# MOSFET_BANK.net
KiCad netlist of a schematic drawn in Altium Designer
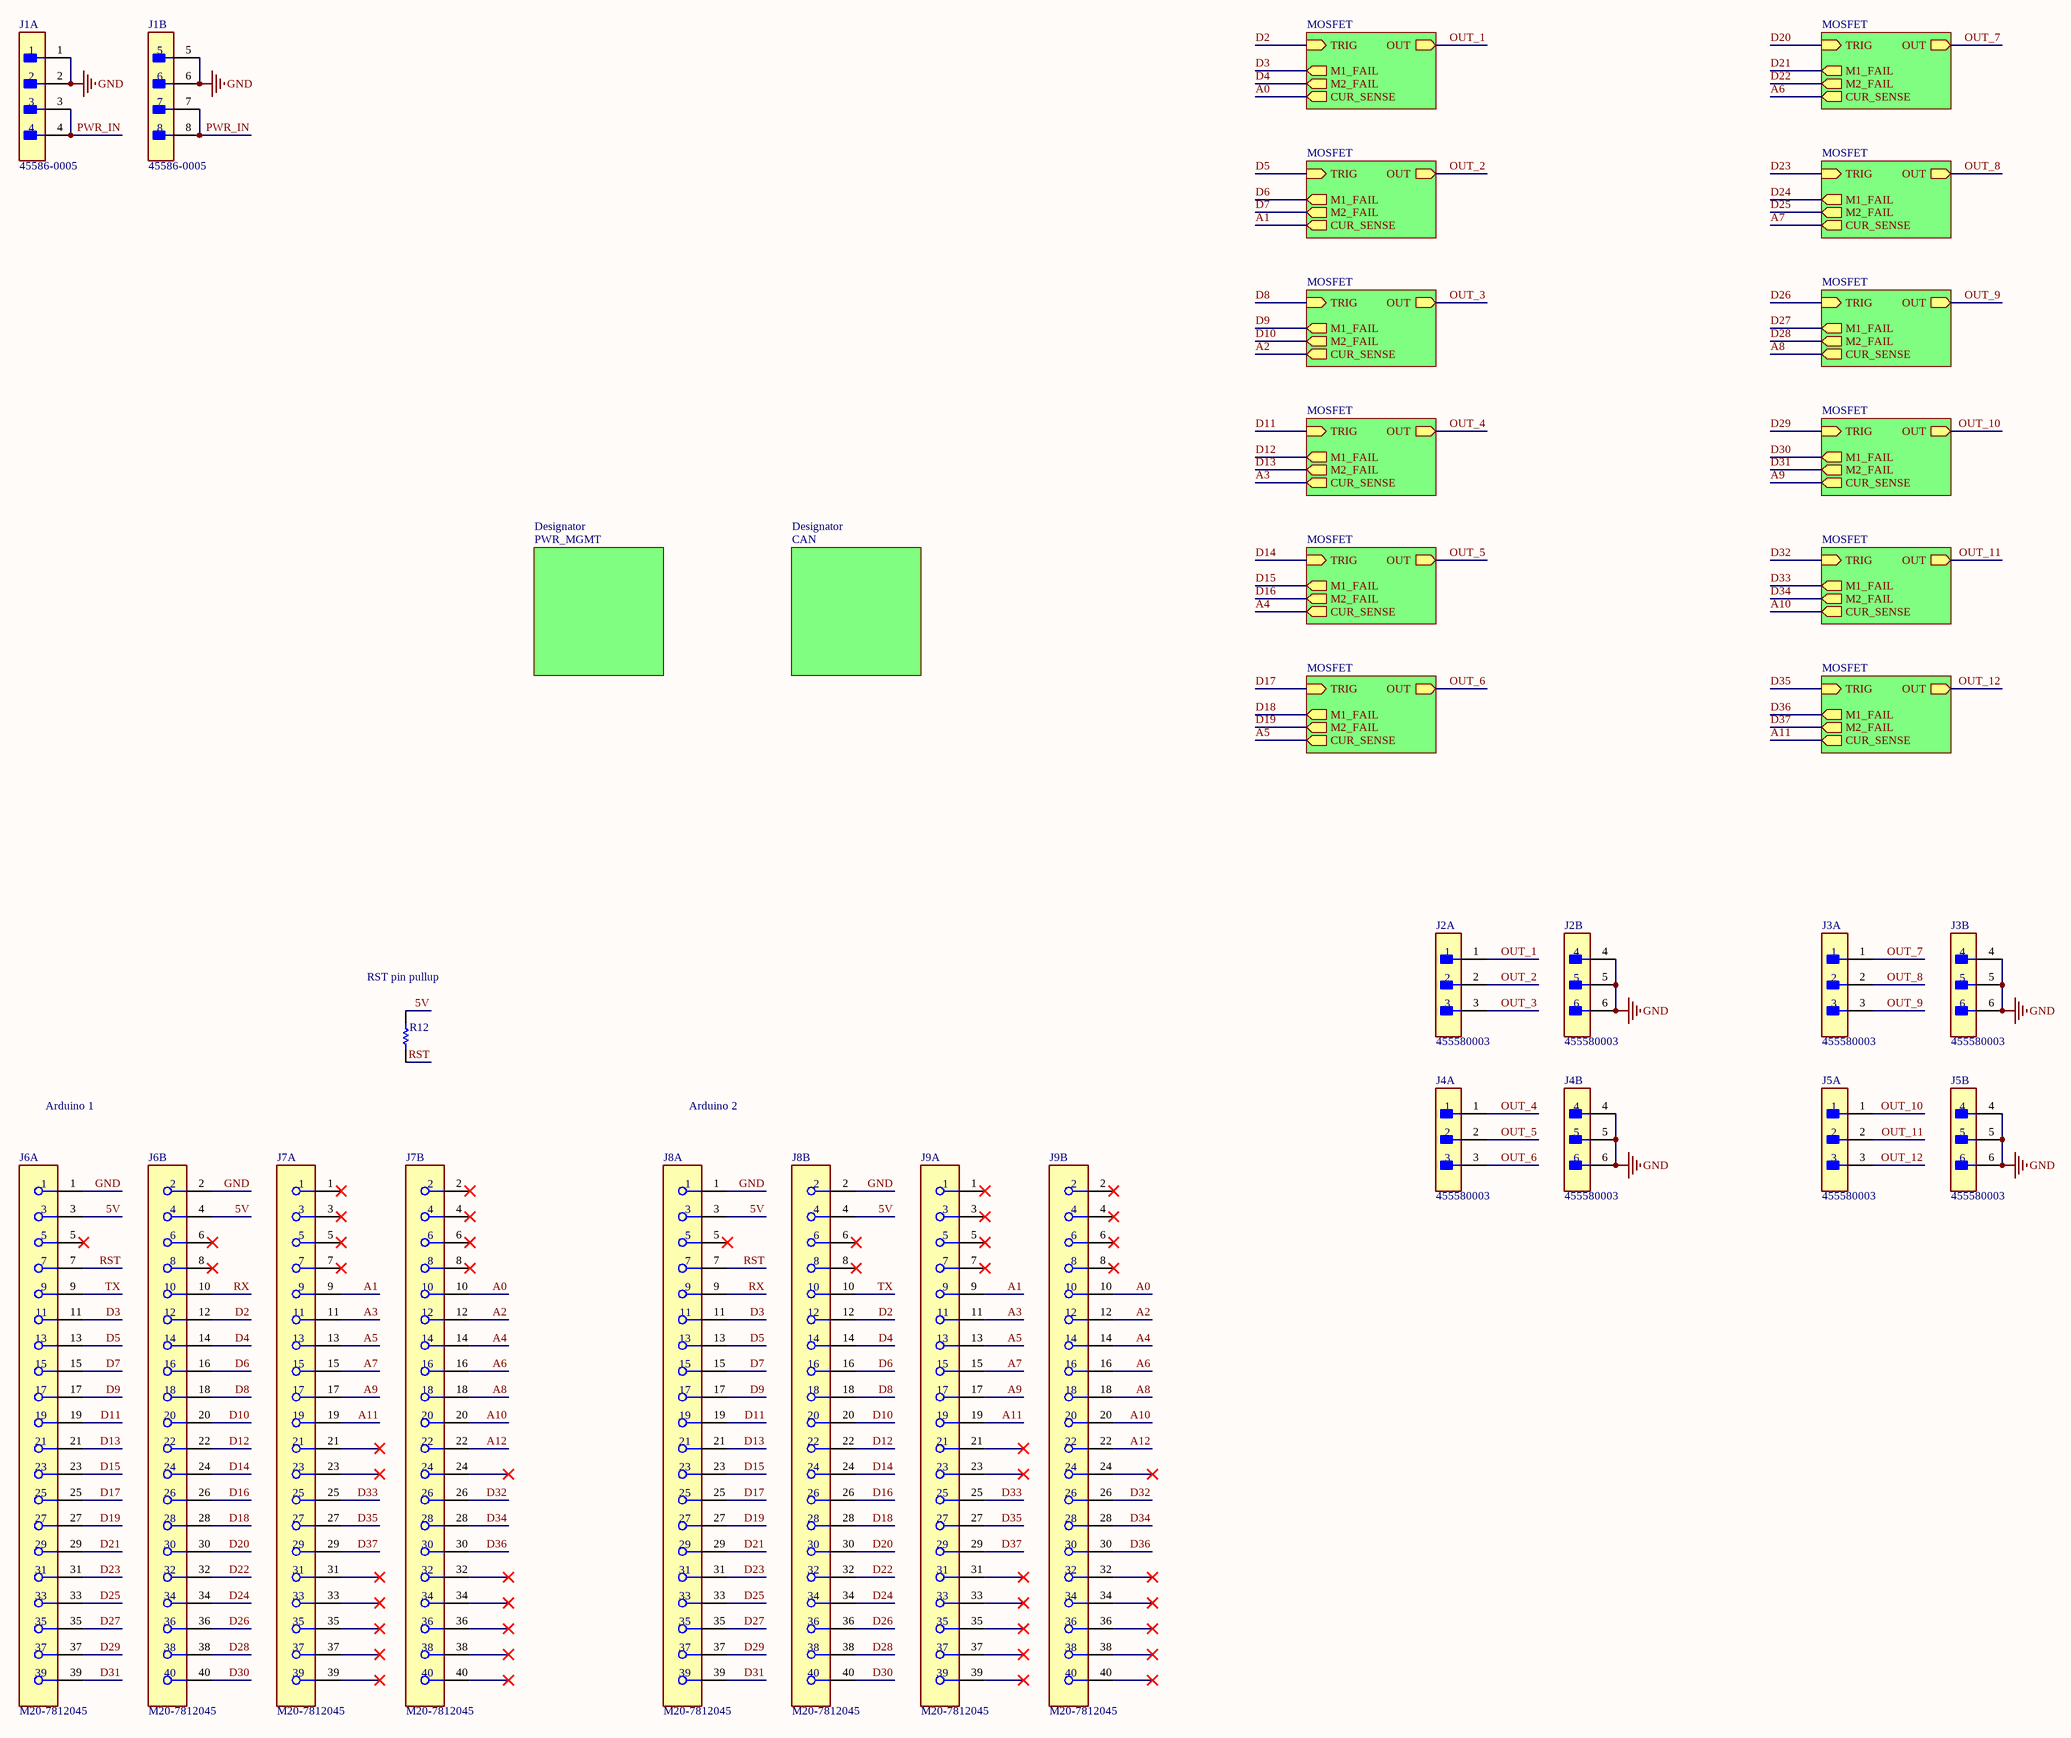
[diagram p0: MOSFET_BANK.SchDoc]

(export (version "E")
  (design (tool "Eeschema 10.0.6"))
  (components
    (comp (ref "J1")
      (value "45586-0005")
      (footprint "FP-45586-0005-MFG")
      (description "CONN HEADER R/A 8POS 4.2MM")
      (libsource (lib "Altium Content Vault") (part "85438c39ca9ef07d43bb2e97c52bc44"))
    )
    (comp (ref "J2")
      (value "455580003")
      (footprint "FP-455580003-MFG")
      (description "CONN HEADER R/A 6POS 4.2MM")
      (fields
        (field (name "OCTOPART") "https://octopart.com/45558-0003-molex-7672845")
        (field (name "MANUFACTURER") "Molex")
      )
      (libsource (lib "Altium Content Vault") (part "bb9cbdb24149a20ba329b4e86909569"))
    )
    (comp (ref "J3")
      (value "455580003")
      (footprint "FP-455580003-MFG")
      (description "CONN HEADER R/A 6POS 4.2MM")
      (fields
        (field (name "OCTOPART") "https://octopart.com/45558-0003-molex-7672845")
        (field (name "MANUFACTURER") "Molex")
      )
      (libsource (lib "Altium Content Vault") (part "bb9cbdb24149a20ba329b4e86909569"))
    )
    (comp (ref "J4")
      (value "455580003")
      (footprint "FP-455580003-MFG")
      (description "CONN HEADER R/A 6POS 4.2MM")
      (fields
        (field (name "OCTOPART") "https://octopart.com/45558-0003-molex-7672845")
        (field (name "MANUFACTURER") "Molex")
      )
      (libsource (lib "Altium Content Vault") (part "bb9cbdb24149a20ba329b4e86909569"))
    )
    (comp (ref "J5")
      (value "455580003")
      (footprint "FP-455580003-MFG")
      (description "CONN HEADER R/A 6POS 4.2MM")
      (fields
        (field (name "OCTOPART") "https://octopart.com/45558-0003-molex-7672845")
        (field (name "MANUFACTURER") "Molex")
      )
      (libsource (lib "Altium Content Vault") (part "bb9cbdb24149a20ba329b4e86909569"))
    )
    (comp (ref "J6")
      (value "M20-7812045")
      (footprint "FP-M20-7812045-MFG")
      (description "CONN RCPT 40POS 0.1 GOLD SMD")
      (libsource (lib "Altium Content Vault") (part "7acf1c4a8db21028d11741a46a6ec78"))
    )
    (comp (ref "J7")
      (value "M20-7812045")
      (footprint "FP-M20-7812045-MFG")
      (description "CONN RCPT 40POS 0.1 GOLD SMD")
      (libsource (lib "Altium Content Vault") (part "7acf1c4a8db21028d11741a46a6ec78"))
    )
    (comp (ref "J8")
      (value "M20-7812045")
      (footprint "FP-M20-7812045-MFG")
      (description "CONN RCPT 40POS 0.1 GOLD SMD")
      (libsource (lib "Altium Content Vault") (part "7acf1c4a8db21028d11741a46a6ec78"))
    )
    (comp (ref "J9")
      (value "M20-7812045")
      (footprint "FP-M20-7812045-MFG")
      (description "CONN RCPT 40POS 0.1 GOLD SMD")
      (libsource (lib "Altium Content Vault") (part "7acf1c4a8db21028d11741a46a6ec78"))
    )
    (comp (ref "R12")
      (value "ERJ3EKF1002V")
      (footprint "RESC1609X55X30LL15T15")
      (description "Chip Resistor, 10 KOhm, +/- 1%, 0.1 W, -55 to 155 degC, 0603 (1608 Metric), RoHS, Tape and Reel")
      (fields (field (name "TOLERANCE") "1%") (field (name "MANUFACTURER") "Panasonic"))
      (libsource (lib "Altium Content Vault") (part "RES-2"))
    )
  )
  (nets
    (net (code "1") (name "/5V") (class "Default")
      (node (ref "J6") (pin "3") (pinfunction "3_3") (pintype "passive"))
      (node (ref "J6") (pin "4") (pinfunction "4_4") (pintype "passive"))
      (node (ref "J8") (pin "3") (pinfunction "3_3") (pintype "passive"))
      (node (ref "J8") (pin "4") (pinfunction "4_4") (pintype "passive"))
      (node (ref "R12") (pin "2") (pinfunction "2_2") (pintype "passive"))
    )
    (net (code "2") (name "/A0") (class "Default")
      (node (ref "J7") (pin "10") (pinfunction "10_10") (pintype "passive"))
      (node (ref "J9") (pin "10") (pinfunction "10_10") (pintype "passive"))
    )
    (net (code "3") (name "/A1") (class "Default")
      (node (ref "J7") (pin "9") (pinfunction "9_9") (pintype "passive"))
      (node (ref "J9") (pin "9") (pinfunction "9_9") (pintype "passive"))
    )
    (net (code "4") (name "/A2") (class "Default")
      (node (ref "J7") (pin "12") (pinfunction "12_12") (pintype "passive"))
      (node (ref "J9") (pin "12") (pinfunction "12_12") (pintype "passive"))
    )
    (net (code "5") (name "/A3") (class "Default")
      (node (ref "J7") (pin "11") (pinfunction "11_11") (pintype "passive"))
      (node (ref "J9") (pin "11") (pinfunction "11_11") (pintype "passive"))
    )
    (net (code "6") (name "/A4") (class "Default")
      (node (ref "J7") (pin "14") (pinfunction "14_14") (pintype "passive"))
      (node (ref "J9") (pin "14") (pinfunction "14_14") (pintype "passive"))
    )
    (net (code "7") (name "/A5") (class "Default")
      (node (ref "J7") (pin "13") (pinfunction "13_13") (pintype "passive"))
      (node (ref "J9") (pin "13") (pinfunction "13_13") (pintype "passive"))
    )
    (net (code "8") (name "/A6") (class "Default")
      (node (ref "J7") (pin "16") (pinfunction "16_16") (pintype "passive"))
      (node (ref "J9") (pin "16") (pinfunction "16_16") (pintype "passive"))
    )
    (net (code "9") (name "/A7") (class "Default")
      (node (ref "J7") (pin "15") (pinfunction "15_15") (pintype "passive"))
      (node (ref "J9") (pin "15") (pinfunction "15_15") (pintype "passive"))
    )
    (net (code "10") (name "/A8") (class "Default")
      (node (ref "J7") (pin "18") (pinfunction "18_18") (pintype "passive"))
      (node (ref "J9") (pin "18") (pinfunction "18_18") (pintype "passive"))
    )
    (net (code "11") (name "/A9") (class "Default")
      (node (ref "J7") (pin "17") (pinfunction "17_17") (pintype "passive"))
      (node (ref "J9") (pin "17") (pinfunction "17_17") (pintype "passive"))
    )
    (net (code "12") (name "/A10") (class "Default")
      (node (ref "J7") (pin "20") (pinfunction "20_20") (pintype "passive"))
      (node (ref "J9") (pin "20") (pinfunction "20_20") (pintype "passive"))
    )
    (net (code "13") (name "/A11") (class "Default")
      (node (ref "J7") (pin "19") (pinfunction "19_19") (pintype "passive"))
      (node (ref "J9") (pin "19") (pinfunction "19_19") (pintype "passive"))
    )
    (net (code "14") (name "/A12") (class "Default")
      (node (ref "J7") (pin "22") (pinfunction "22_22") (pintype "passive"))
      (node (ref "J9") (pin "22") (pinfunction "22_22") (pintype "passive"))
    )
    (net (code "15") (name "/D2") (class "Default")
      (node (ref "J6") (pin "12") (pinfunction "12_12") (pintype "passive"))
      (node (ref "J8") (pin "12") (pinfunction "12_12") (pintype "passive"))
    )
    (net (code "16") (name "/D3") (class "Default")
      (node (ref "J6") (pin "11") (pinfunction "11_11") (pintype "passive"))
      (node (ref "J8") (pin "11") (pinfunction "11_11") (pintype "passive"))
    )
    (net (code "17") (name "/D4") (class "Default")
      (node (ref "J6") (pin "14") (pinfunction "14_14") (pintype "passive"))
      (node (ref "J8") (pin "14") (pinfunction "14_14") (pintype "passive"))
    )
    (net (code "18") (name "/D5") (class "Default")
      (node (ref "J6") (pin "13") (pinfunction "13_13") (pintype "passive"))
      (node (ref "J8") (pin "13") (pinfunction "13_13") (pintype "passive"))
    )
    (net (code "19") (name "/D6") (class "Default")
      (node (ref "J6") (pin "16") (pinfunction "16_16") (pintype "passive"))
      (node (ref "J8") (pin "16") (pinfunction "16_16") (pintype "passive"))
    )
    (net (code "20") (name "/D7") (class "Default")
      (node (ref "J6") (pin "15") (pinfunction "15_15") (pintype "passive"))
      (node (ref "J8") (pin "15") (pinfunction "15_15") (pintype "passive"))
    )
    (net (code "21") (name "/D8") (class "Default")
      (node (ref "J6") (pin "18") (pinfunction "18_18") (pintype "passive"))
      (node (ref "J8") (pin "18") (pinfunction "18_18") (pintype "passive"))
    )
    (net (code "22") (name "/D9") (class "Default")
      (node (ref "J6") (pin "17") (pinfunction "17_17") (pintype "passive"))
      (node (ref "J8") (pin "17") (pinfunction "17_17") (pintype "passive"))
    )
    (net (code "23") (name "/D10") (class "Default")
      (node (ref "J6") (pin "20") (pinfunction "20_20") (pintype "passive"))
      (node (ref "J8") (pin "20") (pinfunction "20_20") (pintype "passive"))
    )
    (net (code "24") (name "/D11") (class "Default")
      (node (ref "J6") (pin "19") (pinfunction "19_19") (pintype "passive"))
      (node (ref "J8") (pin "19") (pinfunction "19_19") (pintype "passive"))
    )
    (net (code "25") (name "/D12") (class "Default")
      (node (ref "J6") (pin "22") (pinfunction "22_22") (pintype "passive"))
      (node (ref "J8") (pin "22") (pinfunction "22_22") (pintype "passive"))
    )
    (net (code "26") (name "/D13") (class "Default")
      (node (ref "J6") (pin "21") (pinfunction "21_21") (pintype "passive"))
      (node (ref "J8") (pin "21") (pinfunction "21_21") (pintype "passive"))
    )
    (net (code "27") (name "/D14") (class "Default")
      (node (ref "J6") (pin "24") (pinfunction "24_24") (pintype "passive"))
      (node (ref "J8") (pin "24") (pinfunction "24_24") (pintype "passive"))
    )
    (net (code "28") (name "/D15") (class "Default")
      (node (ref "J6") (pin "23") (pinfunction "23_23") (pintype "passive"))
      (node (ref "J8") (pin "23") (pinfunction "23_23") (pintype "passive"))
    )
    (net (code "29") (name "/D16") (class "Default")
      (node (ref "J6") (pin "26") (pinfunction "26_26") (pintype "passive"))
      (node (ref "J8") (pin "26") (pinfunction "26_26") (pintype "passive"))
    )
    (net (code "30") (name "/D17") (class "Default")
      (node (ref "J6") (pin "25") (pinfunction "25_25") (pintype "passive"))
      (node (ref "J8") (pin "25") (pinfunction "25_25") (pintype "passive"))
    )
    (net (code "31") (name "/D18") (class "Default")
      (node (ref "J6") (pin "28") (pinfunction "28_28") (pintype "passive"))
      (node (ref "J8") (pin "28") (pinfunction "28_28") (pintype "passive"))
    )
    (net (code "32") (name "/D19") (class "Default")
      (node (ref "J6") (pin "27") (pinfunction "27_27") (pintype "passive"))
      (node (ref "J8") (pin "27") (pinfunction "27_27") (pintype "passive"))
    )
    (net (code "33") (name "/D20") (class "Default")
      (node (ref "J6") (pin "30") (pinfunction "30_30") (pintype "passive"))
      (node (ref "J8") (pin "30") (pinfunction "30_30") (pintype "passive"))
    )
    (net (code "34") (name "/D21") (class "Default")
      (node (ref "J6") (pin "29") (pinfunction "29_29") (pintype "passive"))
      (node (ref "J8") (pin "29") (pinfunction "29_29") (pintype "passive"))
    )
    (net (code "35") (name "/D22") (class "Default")
      (node (ref "J6") (pin "32") (pinfunction "32_32") (pintype "passive"))
      (node (ref "J8") (pin "32") (pinfunction "32_32") (pintype "passive"))
    )
    (net (code "36") (name "/D23") (class "Default")
      (node (ref "J6") (pin "31") (pinfunction "31_31") (pintype "passive"))
      (node (ref "J8") (pin "31") (pinfunction "31_31") (pintype "passive"))
    )
    (net (code "37") (name "/D24") (class "Default")
      (node (ref "J6") (pin "34") (pinfunction "34_34") (pintype "passive"))
      (node (ref "J8") (pin "34") (pinfunction "34_34") (pintype "passive"))
    )
    (net (code "38") (name "/D25") (class "Default")
      (node (ref "J6") (pin "33") (pinfunction "33_33") (pintype "passive"))
      (node (ref "J8") (pin "33") (pinfunction "33_33") (pintype "passive"))
    )
    (net (code "39") (name "/D26") (class "Default")
      (node (ref "J6") (pin "36") (pinfunction "36_36") (pintype "passive"))
      (node (ref "J8") (pin "36") (pinfunction "36_36") (pintype "passive"))
    )
    (net (code "40") (name "/D27") (class "Default")
      (node (ref "J6") (pin "35") (pinfunction "35_35") (pintype "passive"))
      (node (ref "J8") (pin "35") (pinfunction "35_35") (pintype "passive"))
    )
    (net (code "41") (name "/D28") (class "Default")
      (node (ref "J6") (pin "38") (pinfunction "38_38") (pintype "passive"))
      (node (ref "J8") (pin "38") (pinfunction "38_38") (pintype "passive"))
    )
    (net (code "42") (name "/D29") (class "Default")
      (node (ref "J6") (pin "37") (pinfunction "37_37") (pintype "passive"))
      (node (ref "J8") (pin "37") (pinfunction "37_37") (pintype "passive"))
    )
    (net (code "43") (name "/D30") (class "Default")
      (node (ref "J6") (pin "40") (pinfunction "40_40") (pintype "passive"))
      (node (ref "J8") (pin "40") (pinfunction "40_40") (pintype "passive"))
    )
    (net (code "44") (name "/D31") (class "Default")
      (node (ref "J6") (pin "39") (pinfunction "39_39") (pintype "passive"))
      (node (ref "J8") (pin "39") (pinfunction "39_39") (pintype "passive"))
    )
    (net (code "45") (name "/D32") (class "Default")
      (node (ref "J7") (pin "26") (pinfunction "26_26") (pintype "passive"))
      (node (ref "J9") (pin "26") (pinfunction "26_26") (pintype "passive"))
    )
    (net (code "46") (name "/D33") (class "Default")
      (node (ref "J7") (pin "25") (pinfunction "25_25") (pintype "passive"))
      (node (ref "J9") (pin "25") (pinfunction "25_25") (pintype "passive"))
    )
    (net (code "47") (name "/D34") (class "Default")
      (node (ref "J7") (pin "28") (pinfunction "28_28") (pintype "passive"))
      (node (ref "J9") (pin "28") (pinfunction "28_28") (pintype "passive"))
    )
    (net (code "48") (name "/D35") (class "Default")
      (node (ref "J7") (pin "27") (pinfunction "27_27") (pintype "passive"))
      (node (ref "J9") (pin "27") (pinfunction "27_27") (pintype "passive"))
    )
    (net (code "49") (name "/D36") (class "Default")
      (node (ref "J7") (pin "30") (pinfunction "30_30") (pintype "passive"))
      (node (ref "J9") (pin "30") (pinfunction "30_30") (pintype "passive"))
    )
    (net (code "50") (name "/D37") (class "Default")
      (node (ref "J7") (pin "29") (pinfunction "29_29") (pintype "passive"))
      (node (ref "J9") (pin "29") (pinfunction "29_29") (pintype "passive"))
    )
    (net (code "51") (name "/OUT_1") (class "Default")
      (node (ref "J2") (pin "1") (pinfunction "1_1") (pintype "passive"))
    )
    (net (code "52") (name "/OUT_2") (class "Default")
      (node (ref "J2") (pin "2") (pinfunction "2_2") (pintype "passive"))
    )
    (net (code "53") (name "/OUT_3") (class "Default")
      (node (ref "J2") (pin "3") (pinfunction "3_3") (pintype "passive"))
    )
    (net (code "54") (name "/OUT_4") (class "Default")
      (node (ref "J4") (pin "1") (pinfunction "1_1") (pintype "passive"))
    )
    (net (code "55") (name "/OUT_5") (class "Default")
      (node (ref "J4") (pin "2") (pinfunction "2_2") (pintype "passive"))
    )
    (net (code "56") (name "/OUT_6") (class "Default")
      (node (ref "J4") (pin "3") (pinfunction "3_3") (pintype "passive"))
    )
    (net (code "57") (name "/OUT_7") (class "Default")
      (node (ref "J3") (pin "1") (pinfunction "1_1") (pintype "passive"))
    )
    (net (code "58") (name "/OUT_8") (class "Default")
      (node (ref "J3") (pin "2") (pinfunction "2_2") (pintype "passive"))
    )
    (net (code "59") (name "/OUT_9") (class "Default")
      (node (ref "J3") (pin "3") (pinfunction "3_3") (pintype "passive"))
    )
    (net (code "60") (name "/OUT_10") (class "Default")
      (node (ref "J5") (pin "1") (pinfunction "1_1") (pintype "passive"))
    )
    (net (code "61") (name "/OUT_11") (class "Default")
      (node (ref "J5") (pin "2") (pinfunction "2_2") (pintype "passive"))
    )
    (net (code "62") (name "/OUT_12") (class "Default")
      (node (ref "J5") (pin "3") (pinfunction "3_3") (pintype "passive"))
    )
    (net (code "63") (name "/PWR_IN") (class "Default")
      (node (ref "J1") (pin "3") (pinfunction "3_3") (pintype "passive"))
      (node (ref "J1") (pin "4") (pinfunction "4_4") (pintype "passive"))
      (node (ref "J1") (pin "7") (pinfunction "7_7") (pintype "passive"))
      (node (ref "J1") (pin "8") (pinfunction "8_8") (pintype "passive"))
    )
    (net (code "64") (name "/RST") (class "Default")
      (node (ref "J6") (pin "7") (pinfunction "7_7") (pintype "passive"))
      (node (ref "J8") (pin "7") (pinfunction "7_7") (pintype "passive"))
      (node (ref "R12") (pin "1") (pinfunction "1_1") (pintype "passive"))
    )
    (net (code "65") (name "/RX") (class "Default")
      (node (ref "J6") (pin "10") (pinfunction "10_10") (pintype "passive"))
      (node (ref "J8") (pin "9") (pinfunction "9_9") (pintype "passive"))
    )
    (net (code "66") (name "/TX") (class "Default")
      (node (ref "J6") (pin "9") (pinfunction "9_9") (pintype "passive"))
      (node (ref "J8") (pin "10") (pinfunction "10_10") (pintype "passive"))
    )
    (net (code "67") (name "GND") (class "Default")
      (node (ref "J1") (pin "1") (pinfunction "1_1") (pintype "passive"))
      (node (ref "J1") (pin "2") (pinfunction "2_2") (pintype "passive"))
      (node (ref "J1") (pin "5") (pinfunction "5_5") (pintype "passive"))
      (node (ref "J1") (pin "6") (pinfunction "6_6") (pintype "passive"))
      (node (ref "J2") (pin "4") (pinfunction "4_4") (pintype "passive"))
      (node (ref "J2") (pin "5") (pinfunction "5_5") (pintype "passive"))
      (node (ref "J2") (pin "6") (pinfunction "6_6") (pintype "passive"))
      (node (ref "J3") (pin "4") (pinfunction "4_4") (pintype "passive"))
      (node (ref "J3") (pin "5") (pinfunction "5_5") (pintype "passive"))
      (node (ref "J3") (pin "6") (pinfunction "6_6") (pintype "passive"))
      (node (ref "J4") (pin "4") (pinfunction "4_4") (pintype "passive"))
      (node (ref "J4") (pin "5") (pinfunction "5_5") (pintype "passive"))
      (node (ref "J4") (pin "6") (pinfunction "6_6") (pintype "passive"))
      (node (ref "J5") (pin "4") (pinfunction "4_4") (pintype "passive"))
      (node (ref "J5") (pin "5") (pinfunction "5_5") (pintype "passive"))
      (node (ref "J5") (pin "6") (pinfunction "6_6") (pintype "passive"))
      (node (ref "J6") (pin "1") (pinfunction "1_1") (pintype "passive"))
      (node (ref "J6") (pin "2") (pinfunction "2_2") (pintype "passive"))
      (node (ref "J8") (pin "1") (pinfunction "1_1") (pintype "passive"))
      (node (ref "J8") (pin "2") (pinfunction "2_2") (pintype "passive"))
    )
    (net (code "68") (name "unconnected-(J6-Pad5)") (class "Default")
      (node (ref "J6") (pin "5") (pinfunction "5_5") (pintype "passive+no_connect"))
    )
    (net (code "69") (name "unconnected-(J6-Pad6)") (class "Default")
      (node (ref "J6") (pin "6") (pinfunction "6_6") (pintype "passive+no_connect"))
    )
    (net (code "70") (name "unconnected-(J6-Pad8)") (class "Default")
      (node (ref "J6") (pin "8") (pinfunction "8_8") (pintype "passive+no_connect"))
    )
    (net (code "71") (name "unconnected-(J7-Pad1)") (class "Default")
      (node (ref "J7") (pin "1") (pinfunction "1_1") (pintype "passive+no_connect"))
    )
    (net (code "72") (name "unconnected-(J7-Pad2)") (class "Default")
      (node (ref "J7") (pin "2") (pinfunction "2_2") (pintype "passive+no_connect"))
    )
    (net (code "73") (name "unconnected-(J7-Pad3)") (class "Default")
      (node (ref "J7") (pin "3") (pinfunction "3_3") (pintype "passive+no_connect"))
    )
    (net (code "74") (name "unconnected-(J7-Pad4)") (class "Default")
      (node (ref "J7") (pin "4") (pinfunction "4_4") (pintype "passive+no_connect"))
    )
    (net (code "75") (name "unconnected-(J7-Pad5)") (class "Default")
      (node (ref "J7") (pin "5") (pinfunction "5_5") (pintype "passive+no_connect"))
    )
    (net (code "76") (name "unconnected-(J7-Pad6)") (class "Default")
      (node (ref "J7") (pin "6") (pinfunction "6_6") (pintype "passive+no_connect"))
    )
    (net (code "77") (name "unconnected-(J7-Pad7)") (class "Default")
      (node (ref "J7") (pin "7") (pinfunction "7_7") (pintype "passive+no_connect"))
    )
    (net (code "78") (name "unconnected-(J7-Pad8)") (class "Default")
      (node (ref "J7") (pin "8") (pinfunction "8_8") (pintype "passive+no_connect"))
    )
    (net (code "79") (name "unconnected-(J7-Pad21)") (class "Default")
      (node (ref "J7") (pin "21") (pinfunction "21_21") (pintype "passive+no_connect"))
    )
    (net (code "80") (name "unconnected-(J7-Pad23)") (class "Default")
      (node (ref "J7") (pin "23") (pinfunction "23_23") (pintype "passive+no_connect"))
    )
    (net (code "81") (name "unconnected-(J7-Pad24)") (class "Default")
      (node (ref "J7") (pin "24") (pinfunction "24_24") (pintype "passive+no_connect"))
    )
    (net (code "82") (name "unconnected-(J7-Pad31)") (class "Default")
      (node (ref "J7") (pin "31") (pinfunction "31_31") (pintype "passive+no_connect"))
    )
    (net (code "83") (name "unconnected-(J7-Pad32)") (class "Default")
      (node (ref "J7") (pin "32") (pinfunction "32_32") (pintype "passive+no_connect"))
    )
    (net (code "84") (name "unconnected-(J7-Pad33)") (class "Default")
      (node (ref "J7") (pin "33") (pinfunction "33_33") (pintype "passive+no_connect"))
    )
    (net (code "85") (name "unconnected-(J7-Pad34)") (class "Default")
      (node (ref "J7") (pin "34") (pinfunction "34_34") (pintype "passive+no_connect"))
    )
    (net (code "86") (name "unconnected-(J7-Pad35)") (class "Default")
      (node (ref "J7") (pin "35") (pinfunction "35_35") (pintype "passive+no_connect"))
    )
    (net (code "87") (name "unconnected-(J7-Pad36)") (class "Default")
      (node (ref "J7") (pin "36") (pinfunction "36_36") (pintype "passive+no_connect"))
    )
    (net (code "88") (name "unconnected-(J7-Pad37)") (class "Default")
      (node (ref "J7") (pin "37") (pinfunction "37_37") (pintype "passive+no_connect"))
    )
    (net (code "89") (name "unconnected-(J7-Pad38)") (class "Default")
      (node (ref "J7") (pin "38") (pinfunction "38_38") (pintype "passive+no_connect"))
    )
    (net (code "90") (name "unconnected-(J7-Pad39)") (class "Default")
      (node (ref "J7") (pin "39") (pinfunction "39_39") (pintype "passive+no_connect"))
    )
    (net (code "91") (name "unconnected-(J7-Pad40)") (class "Default")
      (node (ref "J7") (pin "40") (pinfunction "40_40") (pintype "passive+no_connect"))
    )
    (net (code "92") (name "unconnected-(J8-Pad5)") (class "Default")
      (node (ref "J8") (pin "5") (pinfunction "5_5") (pintype "passive+no_connect"))
    )
    (net (code "93") (name "unconnected-(J8-Pad6)") (class "Default")
      (node (ref "J8") (pin "6") (pinfunction "6_6") (pintype "passive+no_connect"))
    )
    (net (code "94") (name "unconnected-(J8-Pad8)") (class "Default")
      (node (ref "J8") (pin "8") (pinfunction "8_8") (pintype "passive+no_connect"))
    )
    (net (code "95") (name "unconnected-(J9-Pad1)") (class "Default")
      (node (ref "J9") (pin "1") (pinfunction "1_1") (pintype "passive+no_connect"))
    )
    (net (code "96") (name "unconnected-(J9-Pad2)") (class "Default")
      (node (ref "J9") (pin "2") (pinfunction "2_2") (pintype "passive+no_connect"))
    )
    (net (code "97") (name "unconnected-(J9-Pad3)") (class "Default")
      (node (ref "J9") (pin "3") (pinfunction "3_3") (pintype "passive+no_connect"))
    )
    (net (code "98") (name "unconnected-(J9-Pad4)") (class "Default")
      (node (ref "J9") (pin "4") (pinfunction "4_4") (pintype "passive+no_connect"))
    )
    (net (code "99") (name "unconnected-(J9-Pad5)") (class "Default")
      (node (ref "J9") (pin "5") (pinfunction "5_5") (pintype "passive+no_connect"))
    )
    (net (code "100") (name "unconnected-(J9-Pad6)") (class "Default")
      (node (ref "J9") (pin "6") (pinfunction "6_6") (pintype "passive+no_connect"))
    )
    (net (code "101") (name "unconnected-(J9-Pad7)") (class "Default")
      (node (ref "J9") (pin "7") (pinfunction "7_7") (pintype "passive+no_connect"))
    )
    (net (code "102") (name "unconnected-(J9-Pad8)") (class "Default")
      (node (ref "J9") (pin "8") (pinfunction "8_8") (pintype "passive+no_connect"))
    )
    (net (code "103") (name "unconnected-(J9-Pad21)") (class "Default")
      (node (ref "J9") (pin "21") (pinfunction "21_21") (pintype "passive+no_connect"))
    )
    (net (code "104") (name "unconnected-(J9-Pad23)") (class "Default")
      (node (ref "J9") (pin "23") (pinfunction "23_23") (pintype "passive+no_connect"))
    )
    (net (code "105") (name "unconnected-(J9-Pad24)") (class "Default")
      (node (ref "J9") (pin "24") (pinfunction "24_24") (pintype "passive+no_connect"))
    )
    (net (code "106") (name "unconnected-(J9-Pad31)") (class "Default")
      (node (ref "J9") (pin "31") (pinfunction "31_31") (pintype "passive+no_connect"))
    )
    (net (code "107") (name "unconnected-(J9-Pad32)") (class "Default")
      (node (ref "J9") (pin "32") (pinfunction "32_32") (pintype "passive+no_connect"))
    )
    (net (code "108") (name "unconnected-(J9-Pad33)") (class "Default")
      (node (ref "J9") (pin "33") (pinfunction "33_33") (pintype "passive+no_connect"))
    )
    (net (code "109") (name "unconnected-(J9-Pad34)") (class "Default")
      (node (ref "J9") (pin "34") (pinfunction "34_34") (pintype "passive+no_connect"))
    )
    (net (code "110") (name "unconnected-(J9-Pad35)") (class "Default")
      (node (ref "J9") (pin "35") (pinfunction "35_35") (pintype "passive+no_connect"))
    )
    (net (code "111") (name "unconnected-(J9-Pad36)") (class "Default")
      (node (ref "J9") (pin "36") (pinfunction "36_36") (pintype "passive+no_connect"))
    )
    (net (code "112") (name "unconnected-(J9-Pad37)") (class "Default")
      (node (ref "J9") (pin "37") (pinfunction "37_37") (pintype "passive+no_connect"))
    )
    (net (code "113") (name "unconnected-(J9-Pad38)") (class "Default")
      (node (ref "J9") (pin "38") (pinfunction "38_38") (pintype "passive+no_connect"))
    )
    (net (code "114") (name "unconnected-(J9-Pad39)") (class "Default")
      (node (ref "J9") (pin "39") (pinfunction "39_39") (pintype "passive+no_connect"))
    )
    (net (code "115") (name "unconnected-(J9-Pad40)") (class "Default")
      (node (ref "J9") (pin "40") (pinfunction "40_40") (pintype "passive+no_connect"))
    )
  )
)
